# ON_OFF_POWER_LED_v2_schematic.net
KiCad netlist of a schematic drawn in Altium Designer
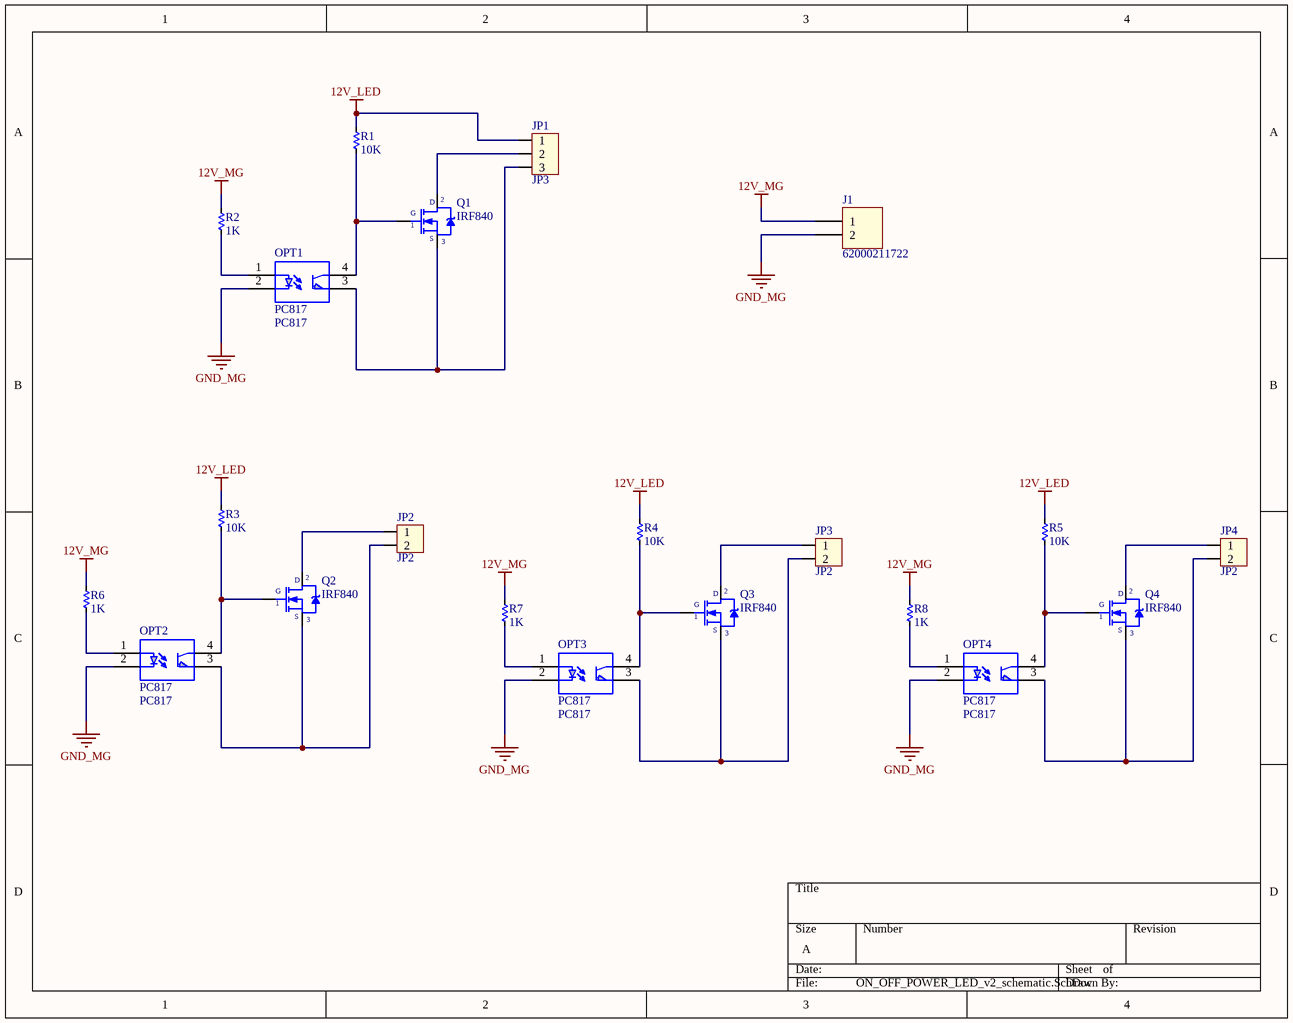
[diagram p0: ON_OFF_POWER_LED_v2_schematic.SchDoc]

(export (version "E")
  (design (tool "Eeschema 10.0.6"))
  (components
    (comp (ref "J1")
      (value "62000211722")
      (footprint "62000211722")
      (description "WR-WTB 2.00mm Male Horizontal Shrouded Header, 2p")
      (fields (field (name "PUBLISHER") "Wurth Elektronik"))
      (libsource (lib "Header2.0") (part "62000211722"))
    )
    (comp (ref "JP1")
      (value "JP3")
      (footprint "CON 3/7.62mm")
      (description "Connector 3")
      (libsource (lib "Tr.Thoai") (part "Con3"))
    )
    (comp (ref "JP2")
      (value "JP2")
      (footprint "CON 2/7.62mm")
      (description "Connector 2")
      (libsource (lib "Tr.Thoai") (part "Con2"))
    )
    (comp (ref "JP3")
      (value "JP2")
      (footprint "CON 2/7.62mm")
      (description "Connector 2")
      (libsource (lib "Tr.Thoai") (part "Con2"))
    )
    (comp (ref "JP4")
      (value "JP2")
      (footprint "CON 2/7.62mm")
      (description "Connector 2")
      (libsource (lib "Tr.Thoai") (part "Con2"))
    )
    (comp (ref "OPT1")
      (value "PC817")
      (footprint "DIP-4 SMD")
      (description "OptoAcoplador 4 terminais")
      (fields (field (name "MODELO") "PC817"))
      (libsource (lib "Altium_Library_Brasil") (part "PC817"))
    )
    (comp (ref "OPT2")
      (value "PC817")
      (footprint "DIP-4 SMD")
      (description "OptoAcoplador 4 terminais")
      (fields (field (name "MODELO") "PC817"))
      (libsource (lib "Altium_Library_Brasil") (part "PC817"))
    )
    (comp (ref "OPT3")
      (value "PC817")
      (footprint "DIP-4 SMD")
      (description "OptoAcoplador 4 terminais")
      (fields (field (name "MODELO") "PC817"))
      (libsource (lib "Altium_Library_Brasil") (part "PC817"))
    )
    (comp (ref "OPT4")
      (value "PC817")
      (footprint "DIP-4 SMD")
      (description "OptoAcoplador 4 terminais")
      (fields (field (name "MODELO") "PC817"))
      (libsource (lib "Altium_Library_Brasil") (part "PC817"))
    )
    (comp (ref "Q1")
      (value "IRF840")
      (footprint "TO220H1")
      (description "MOSFET N - CHANNEL 500V - 0.75 - 8A - TO-220")
      (libsource (lib "LIBRARY") (part "IRF840"))
    )
    (comp (ref "Q2")
      (value "IRF840")
      (footprint "TO220H1")
      (description "MOSFET N - CHANNEL 500V - 0.75 - 8A - TO-220")
      (libsource (lib "LIBRARY") (part "IRF840"))
    )
    (comp (ref "Q3")
      (value "IRF840")
      (footprint "TO220H1")
      (description "MOSFET N - CHANNEL 500V - 0.75 - 8A - TO-220")
      (libsource (lib "LIBRARY") (part "IRF840"))
    )
    (comp (ref "Q4")
      (value "IRF840")
      (footprint "TO220H1")
      (description "MOSFET N - CHANNEL 500V - 0.75 - 8A - TO-220")
      (libsource (lib "LIBRARY") (part "IRF840"))
    )
    (comp (ref "R1")
      (value "10K")
      (footprint "RES-SMD-0805")
      (description "Resistor")
      (fields
        (field (name "MANUFACTURER") "Generic Components")
        (field (name "PUBLISHER") "Altium Hobart Technology Centre")
      )
      (libsource (lib "LIBRARY") (part "Res-SMD"))
    )
    (comp (ref "R2")
      (value "1K")
      (footprint "RES-SMD-0805")
      (description "Resistor")
      (fields
        (field (name "MANUFACTURER") "Generic Components")
        (field (name "PUBLISHER") "Altium Hobart Technology Centre")
      )
      (libsource (lib "LIBRARY") (part "Res-SMD"))
    )
    (comp (ref "R3")
      (value "10K")
      (footprint "RES-SMD-0805")
      (description "Resistor")
      (fields
        (field (name "MANUFACTURER") "Generic Components")
        (field (name "PUBLISHER") "Altium Hobart Technology Centre")
      )
      (libsource (lib "LIBRARY") (part "Res-SMD"))
    )
    (comp (ref "R4")
      (value "10K")
      (footprint "RES-SMD-0805")
      (description "Resistor")
      (fields
        (field (name "MANUFACTURER") "Generic Components")
        (field (name "PUBLISHER") "Altium Hobart Technology Centre")
      )
      (libsource (lib "LIBRARY") (part "Res-SMD"))
    )
    (comp (ref "R5")
      (value "10K")
      (footprint "RES-SMD-0805")
      (description "Resistor")
      (fields
        (field (name "MANUFACTURER") "Generic Components")
        (field (name "PUBLISHER") "Altium Hobart Technology Centre")
      )
      (libsource (lib "LIBRARY") (part "Res-SMD"))
    )
    (comp (ref "R6")
      (value "1K")
      (footprint "RES-SMD-0805")
      (description "Resistor")
      (fields
        (field (name "MANUFACTURER") "Generic Components")
        (field (name "PUBLISHER") "Altium Hobart Technology Centre")
      )
      (libsource (lib "LIBRARY") (part "Res-SMD"))
    )
    (comp (ref "R7")
      (value "1K")
      (footprint "RES-SMD-0805")
      (description "Resistor")
      (fields
        (field (name "MANUFACTURER") "Generic Components")
        (field (name "PUBLISHER") "Altium Hobart Technology Centre")
      )
      (libsource (lib "LIBRARY") (part "Res-SMD"))
    )
    (comp (ref "R8")
      (value "1K")
      (footprint "RES-SMD-0805")
      (description "Resistor")
      (fields
        (field (name "MANUFACTURER") "Generic Components")
        (field (name "PUBLISHER") "Altium Hobart Technology Centre")
      )
      (libsource (lib "LIBRARY") (part "Res-SMD"))
    )
  )
  (nets
    (net (code "1") (name "12V_LED") (class "Default")
      (node (ref "JP1") (pin "1") (pinfunction "1_1") (pintype "passive"))
      (node (ref "R1") (pin "1") (pinfunction "1_1") (pintype "passive"))
      (node (ref "R3") (pin "1") (pinfunction "1_1") (pintype "passive"))
      (node (ref "R4") (pin "1") (pinfunction "1_1") (pintype "passive"))
      (node (ref "R5") (pin "1") (pinfunction "1_1") (pintype "passive"))
    )
    (net (code "2") (name "12V_MG") (class "Default")
      (node (ref "J1") (pin "1") (pinfunction "1_1") (pintype "passive"))
      (node (ref "R2") (pin "1") (pinfunction "1_1") (pintype "passive"))
      (node (ref "R6") (pin "1") (pinfunction "1_1") (pintype "passive"))
      (node (ref "R7") (pin "1") (pinfunction "1_1") (pintype "passive"))
      (node (ref "R8") (pin "1") (pinfunction "1_1") (pintype "passive"))
    )
    (net (code "3") (name "GND_MG") (class "Default")
      (node (ref "J1") (pin "2") (pinfunction "2_2") (pintype "passive"))
      (node (ref "OPT1") (pin "2") (pinfunction "K_2") (pintype "passive"))
      (node (ref "OPT2") (pin "2") (pinfunction "K_2") (pintype "passive"))
      (node (ref "OPT3") (pin "2") (pinfunction "K_2") (pintype "passive"))
      (node (ref "OPT4") (pin "2") (pinfunction "K_2") (pintype "passive"))
    )
    (net (code "4") (name "Net-(OPT1-A)") (class "Default")
      (node (ref "OPT1") (pin "1") (pinfunction "A_1") (pintype "passive"))
      (node (ref "R2") (pin "2") (pinfunction "2_2") (pintype "passive"))
    )
    (net (code "5") (name "Net-(OPT1-COLETOR)") (class "Default")
      (node (ref "OPT1") (pin "4") (pinfunction "COLETOR_4") (pintype "passive"))
      (node (ref "Q1") (pin "1") (pinfunction "G_1") (pintype "passive"))
      (node (ref "R1") (pin "2") (pinfunction "2_2") (pintype "passive"))
    )
    (net (code "6") (name "Net-(OPT1-EMISSOR)") (class "Default")
      (node (ref "JP1") (pin "3") (pinfunction "3_3") (pintype "passive"))
      (node (ref "OPT1") (pin "3") (pinfunction "EMISSOR_3") (pintype "passive"))
      (node (ref "Q1") (pin "3") (pinfunction "S_3") (pintype "passive"))
    )
    (net (code "7") (name "Net-(OPT2-A)") (class "Default")
      (node (ref "OPT2") (pin "1") (pinfunction "A_1") (pintype "passive"))
      (node (ref "R6") (pin "2") (pinfunction "2_2") (pintype "passive"))
    )
    (net (code "8") (name "Net-(OPT2-COLETOR)") (class "Default")
      (node (ref "OPT2") (pin "4") (pinfunction "COLETOR_4") (pintype "passive"))
      (node (ref "Q2") (pin "1") (pinfunction "G_1") (pintype "passive"))
      (node (ref "R3") (pin "2") (pinfunction "2_2") (pintype "passive"))
    )
    (net (code "9") (name "Net-(OPT2-EMISSOR)") (class "Default")
      (node (ref "JP2") (pin "2") (pinfunction "2_2") (pintype "passive"))
      (node (ref "OPT2") (pin "3") (pinfunction "EMISSOR_3") (pintype "passive"))
      (node (ref "Q2") (pin "3") (pinfunction "S_3") (pintype "passive"))
    )
    (net (code "10") (name "Net-(OPT3-A)") (class "Default")
      (node (ref "OPT3") (pin "1") (pinfunction "A_1") (pintype "passive"))
      (node (ref "R7") (pin "2") (pinfunction "2_2") (pintype "passive"))
    )
    (net (code "11") (name "Net-(OPT3-COLETOR)") (class "Default")
      (node (ref "OPT3") (pin "4") (pinfunction "COLETOR_4") (pintype "passive"))
      (node (ref "Q3") (pin "1") (pinfunction "G_1") (pintype "passive"))
      (node (ref "R4") (pin "2") (pinfunction "2_2") (pintype "passive"))
    )
    (net (code "12") (name "Net-(OPT3-EMISSOR)") (class "Default")
      (node (ref "JP3") (pin "2") (pinfunction "2_2") (pintype "passive"))
      (node (ref "OPT3") (pin "3") (pinfunction "EMISSOR_3") (pintype "passive"))
      (node (ref "Q3") (pin "3") (pinfunction "S_3") (pintype "passive"))
    )
    (net (code "13") (name "Net-(OPT4-A)") (class "Default")
      (node (ref "OPT4") (pin "1") (pinfunction "A_1") (pintype "passive"))
      (node (ref "R8") (pin "2") (pinfunction "2_2") (pintype "passive"))
    )
    (net (code "14") (name "Net-(OPT4-COLETOR)") (class "Default")
      (node (ref "OPT4") (pin "4") (pinfunction "COLETOR_4") (pintype "passive"))
      (node (ref "Q4") (pin "1") (pinfunction "G_1") (pintype "passive"))
      (node (ref "R5") (pin "2") (pinfunction "2_2") (pintype "passive"))
    )
    (net (code "15") (name "Net-(OPT4-EMISSOR)") (class "Default")
      (node (ref "JP4") (pin "2") (pinfunction "2_2") (pintype "passive"))
      (node (ref "OPT4") (pin "3") (pinfunction "EMISSOR_3") (pintype "passive"))
      (node (ref "Q4") (pin "3") (pinfunction "S_3") (pintype "passive"))
    )
    (net (code "16") (name "Net-(Q1-D)") (class "Default")
      (node (ref "JP1") (pin "2") (pinfunction "2_2") (pintype "passive"))
      (node (ref "Q1") (pin "2") (pinfunction "D_2") (pintype "passive"))
    )
    (net (code "17") (name "Net-(Q2-D)") (class "Default")
      (node (ref "JP2") (pin "1") (pinfunction "1_1") (pintype "passive"))
      (node (ref "Q2") (pin "2") (pinfunction "D_2") (pintype "passive"))
    )
    (net (code "18") (name "Net-(Q3-D)") (class "Default")
      (node (ref "JP3") (pin "1") (pinfunction "1_1") (pintype "passive"))
      (node (ref "Q3") (pin "2") (pinfunction "D_2") (pintype "passive"))
    )
    (net (code "19") (name "Net-(Q4-D)") (class "Default")
      (node (ref "JP4") (pin "1") (pinfunction "1_1") (pintype "passive"))
      (node (ref "Q4") (pin "2") (pinfunction "D_2") (pintype "passive"))
    )
  )
)
